# Cell.net
KiCad netlist of a schematic drawn in Altium Designer
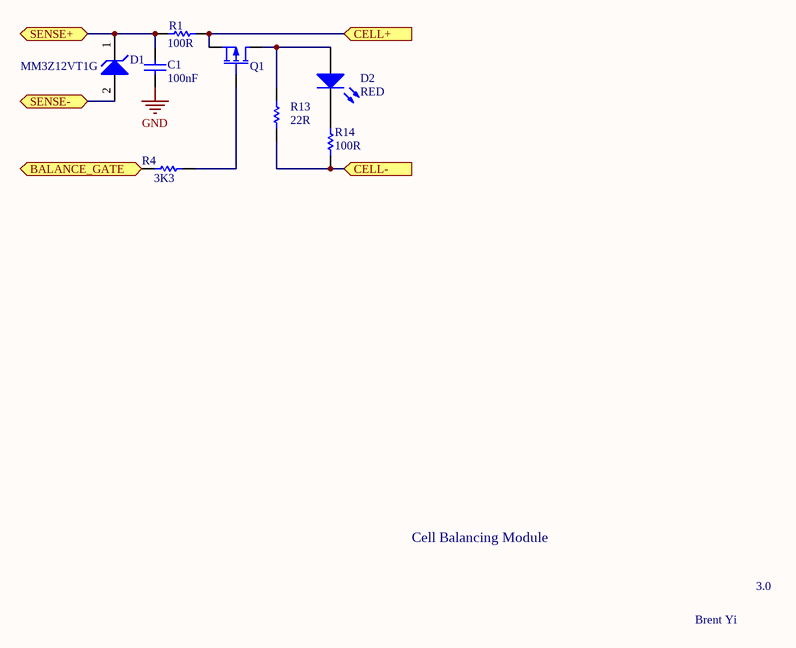
[diagram p0: Cell.SchDoc]

(export (version "E")
  (design (tool "Eeschema 10.0.6"))
  (components
    (comp (ref "C1")
      (value "100nF")
      (footprint "CAPC0603(1608)100_M")
      (description "CAP 100nF 6.3V Â±5% 0603 (1608 Metric) Thickness 1mm SMD")
      (fields (field (name "TOLERANCE") "Â±5%"))
      (libsource (lib "Altium Content Vault") (part "CAP"))
    )
    (comp (ref "D1")
      (value "MM3Z12VT1G")
      (footprint "ONSC-SOD-323-2-477-02_V")
      (description "Zener Voltage Regulator, 300 mW, 2-Pin SOD-323, Tape and Reel")
      (fields (field (name "MANUFACTURER") "On Semiconductor") (field (name "PARTNUMBER") "MM3Z12VT1"))
      (libsource (lib "Altium Content Vault") (part "CMP-1060-00726-1"))
    )
    (comp (ref "D2")
      (value "RED")
      (footprint "0603_A")
      (description "SMD mono-color Chip LED, WL-SMCW, Red")
      (fields (field (name "MANUFACTURER") "Wuerth Elektronik") (field (name "PARTNUMBER") "150060RS75000"))
      (libsource (lib "Altium Content Vault") (part "CMP-1426-00001-1"))
    )
    (comp (ref "Q1")
      (value "SI2365")
      (footprint "SOT23-3")
      (description "P-Channel MOSFET")
      (fields (field (name "PUBLISHER") "Altium Limited"))
      (libsource (lib "Components") (part "MOSFET-P"))
    )
    (comp (ref "R1")
      (value "100R")
      (footprint "RESC0603(1608)_N")
      (description "100R 0.1W 5% 0603 (1608 Metric)  SMD")
      (fields (field (name "TOLERANCE") "5 %") (field (name "POWER") "0.1 W"))
      (libsource (lib "Altium Content Vault") (part "CMP-1012-00050-1"))
    )
    (comp (ref "R4")
      (value "3K3")
      (footprint "RESC0603(1608)_N")
      (description "3K3 0.1W 5% 0603 (1608 Metric)  SMD")
      (fields (field (name "TOLERANCE") "5 %") (field (name "POWER") "0.1 W"))
      (libsource (lib "Altium Content Vault") (part "RES"))
    )
    (comp (ref "R13")
      (value "22R")
      (footprint "RESC2512(6432)_N")
      (description "10R 1W 5% 2512 (6432 Metric)  SMD")
      (fields (field (name "TOLERANCE") "5 %") (field (name "POWER") "1 W"))
      (libsource (lib "Altium Content Vault") (part "RES"))
    )
    (comp (ref "R14")
      (value "100R")
      (footprint "RESC0603(1608)_N")
      (description "100R 0.1W 5% 0603 (1608 Metric)  SMD")
      (fields (field (name "TOLERANCE") "5 %") (field (name "POWER") "0.1 W"))
      (libsource (lib "Altium Content Vault") (part "CMP-1012-00050-1"))
    )
  )
  (nets
    (net (code "1") (name "/BALANCE_GATE") (class "Default")
      (node (ref "R4") (pin "1") (pinfunction "1_1") (pintype "passive"))
    )
    (net (code "2") (name "/CELL+") (class "Default")
      (node (ref "Q1") (pin "3") (pinfunction "S_3") (pintype "passive"))
      (node (ref "R1") (pin "2") (pinfunction "2_2") (pintype "passive"))
    )
    (net (code "3") (name "/CELL-") (class "Default")
      (node (ref "R13") (pin "2") (pinfunction "2_2") (pintype "passive"))
      (node (ref "R14") (pin "1") (pinfunction "1_1") (pintype "passive"))
    )
    (net (code "4") (name "/SENSE+") (class "Default")
      (node (ref "C1") (pin "1") (pinfunction "1_1") (pintype "passive"))
      (node (ref "D1") (pin "1") (pinfunction "K_1") (pintype "passive"))
      (node (ref "R1") (pin "1") (pinfunction "1_1") (pintype "passive"))
    )
    (net (code "5") (name "/SENSE-") (class "Default")
      (node (ref "D1") (pin "2") (pinfunction "A_2") (pintype "passive"))
    )
    (net (code "6") (name "GND") (class "Default")
      (node (ref "C1") (pin "2") (pinfunction "2_2") (pintype "passive"))
    )
    (net (code "7") (name "Net-(D2-A)") (class "Default")
      (node (ref "D2") (pin "2") (pinfunction "A_2") (pintype "passive"))
      (node (ref "Q1") (pin "2") (pinfunction "D_2") (pintype "passive"))
      (node (ref "R13") (pin "1") (pinfunction "1_1") (pintype "passive"))
    )
    (net (code "8") (name "Net-(D2-K)") (class "Default")
      (node (ref "D2") (pin "1") (pinfunction "K_1") (pintype "passive"))
      (node (ref "R14") (pin "2") (pinfunction "2_2") (pintype "passive"))
    )
    (net (code "9") (name "Net-(Q1-G)") (class "Default")
      (node (ref "Q1") (pin "1") (pinfunction "G_1") (pintype "passive"))
      (node (ref "R4") (pin "2") (pinfunction "2_2") (pintype "passive"))
    )
  )
)
